# Strain_Gauge_Amplifier.net
KiCad netlist of a schematic drawn in EAGLE
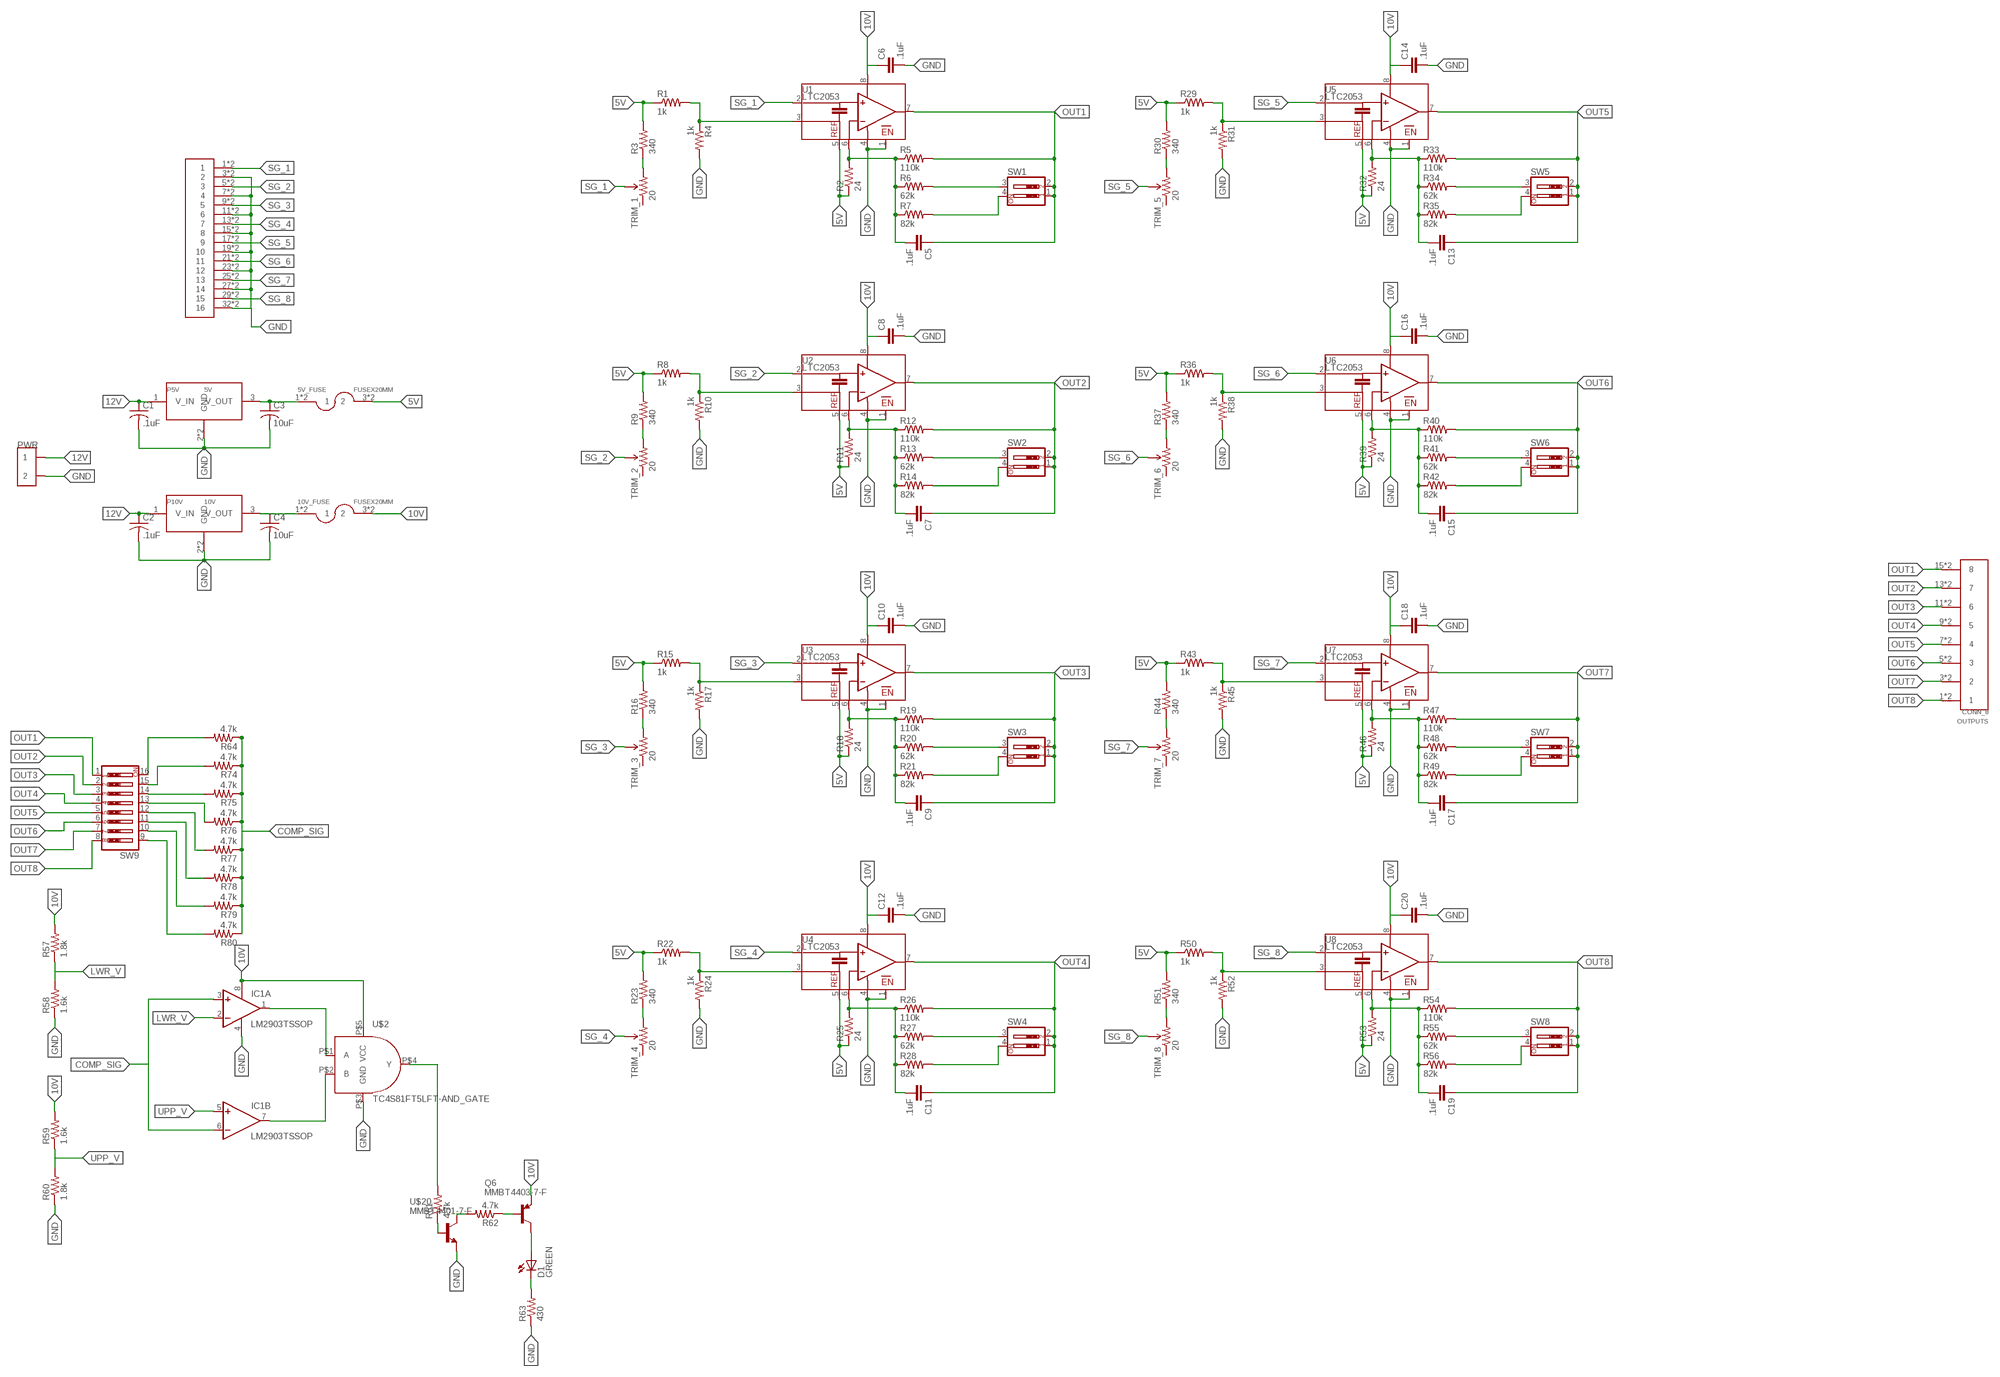
[diagram p0: schematic, sheet 1]

(export (version "E")
  (design (tool "Eeschema 10.0.6"))
  (components
    (comp (ref "5V_FUSE")
      (value "FUSEX20MM")
      (footprint "eagle-import:FUSE_5MM")
      (libsource (lib "eagle-import") (part "FUSEX20MM"))
    )
    (comp (ref "10V_FUSE")
      (value "FUSEX20MM")
      (footprint "eagle-import:FUSE_5MM")
      (libsource (lib "eagle-import") (part "FUSEX20MM"))
    )
    (comp (ref "C1")
      (value ".1uF")
      (footprint "eagle-import:C0603")
      (libsource (lib "eagle-import") (part "C-USC0603"))
    )
    (comp (ref "C2")
      (value ".1uF")
      (footprint "eagle-import:C0603")
      (libsource (lib "eagle-import") (part "C-USC0603"))
    )
    (comp (ref "C3")
      (value "10uF")
      (footprint "eagle-import:C1206")
      (libsource (lib "eagle-import") (part "C-USC1206"))
    )
    (comp (ref "C4")
      (value "10uF")
      (footprint "eagle-import:C1206")
      (libsource (lib "eagle-import") (part "C-USC1206"))
    )
    (comp (ref "C5")
      (value ".1uF")
      (footprint "eagle-import:0603-CAP")
      (libsource (lib "eagle-import") (part "CAP0603-CAP"))
    )
    (comp (ref "C6")
      (value ".1uF")
      (footprint "eagle-import:0603-CAP")
      (libsource (lib "eagle-import") (part "CAP0603-CAP"))
    )
    (comp (ref "C7")
      (value ".1uF")
      (footprint "eagle-import:0603-CAP")
      (libsource (lib "eagle-import") (part "CAP0603-CAP"))
    )
    (comp (ref "C8")
      (value ".1uF")
      (footprint "eagle-import:0603-CAP")
      (libsource (lib "eagle-import") (part "CAP0603-CAP"))
    )
    (comp (ref "C9")
      (value ".1uF")
      (footprint "eagle-import:0603-CAP")
      (libsource (lib "eagle-import") (part "CAP0603-CAP"))
    )
    (comp (ref "C10")
      (value ".1uF")
      (footprint "eagle-import:0603-CAP")
      (libsource (lib "eagle-import") (part "CAP0603-CAP"))
    )
    (comp (ref "C11")
      (value ".1uF")
      (footprint "eagle-import:0603-CAP")
      (libsource (lib "eagle-import") (part "CAP0603-CAP"))
    )
    (comp (ref "C12")
      (value ".1uF")
      (footprint "eagle-import:0603-CAP")
      (libsource (lib "eagle-import") (part "CAP0603-CAP"))
    )
    (comp (ref "C13")
      (value ".1uF")
      (footprint "eagle-import:0603-CAP")
      (libsource (lib "eagle-import") (part "CAP0603-CAP"))
    )
    (comp (ref "C14")
      (value ".1uF")
      (footprint "eagle-import:0603-CAP")
      (libsource (lib "eagle-import") (part "CAP0603-CAP"))
    )
    (comp (ref "C15")
      (value ".1uF")
      (footprint "eagle-import:0603-CAP")
      (libsource (lib "eagle-import") (part "CAP0603-CAP"))
    )
    (comp (ref "C16")
      (value ".1uF")
      (footprint "eagle-import:0603-CAP")
      (libsource (lib "eagle-import") (part "CAP0603-CAP"))
    )
    (comp (ref "C17")
      (value ".1uF")
      (footprint "eagle-import:0603-CAP")
      (libsource (lib "eagle-import") (part "CAP0603-CAP"))
    )
    (comp (ref "C18")
      (value ".1uF")
      (footprint "eagle-import:0603-CAP")
      (libsource (lib "eagle-import") (part "CAP0603-CAP"))
    )
    (comp (ref "C19")
      (value ".1uF")
      (footprint "eagle-import:0603-CAP")
      (libsource (lib "eagle-import") (part "CAP0603-CAP"))
    )
    (comp (ref "C20")
      (value ".1uF")
      (footprint "eagle-import:0603-CAP")
      (libsource (lib "eagle-import") (part "CAP0603-CAP"))
    )
    (comp (ref "D1")
      (value "GREEN")
      (footprint "eagle-import:LED-0603")
      (libsource (lib "eagle-import") (part "LED-GREEN0603"))
    )
    (comp (ref "IC1")
      (value "LM2903TSSOP")
      (footprint "eagle-import:TSSOP8")
      (libsource (lib "eagle-import") (part "LM2903TSSOP"))
    )
    (comp (ref "OUTPUTS")
      (value "CONN_8")
      (footprint "eagle-import:CONNECTOR_8")
      (libsource (lib "eagle-import") (part "CONN_8"))
    )
    (comp (ref "P5V")
      (value "5V")
      (footprint "eagle-import:SOT223")
      (libsource (lib "eagle-import") (part "LM2937"))
    )
    (comp (ref "P10V")
      (value "10V")
      (footprint "eagle-import:SOT223")
      (libsource (lib "eagle-import") (part "LM2937"))
    )
    (comp (ref "PWR")
      (value "CONN_2")
      (footprint "eagle-import:CONNECTOR_2")
      (libsource (lib "eagle-import") (part "CONN_2"))
    )
    (comp (ref "Q6")
      (value "MMBT4403-7-F")
      (footprint "eagle-import:SOT-23-3")
      (libsource (lib "eagle-import") (part "MMBT4403-7-F"))
    )
    (comp (ref "R1")
      (value "1k")
      (footprint "eagle-import:0603-RES")
      (libsource (lib "eagle-import") (part "RESISTOR0603"))
    )
    (comp (ref "R2")
      (value "24")
      (footprint "eagle-import:0603-RES")
      (libsource (lib "eagle-import") (part "RESISTOR0603"))
    )
    (comp (ref "R3")
      (value "340")
      (footprint "eagle-import:0603-RES")
      (libsource (lib "eagle-import") (part "RESISTOR0603"))
    )
    (comp (ref "R4")
      (value "1k")
      (footprint "eagle-import:0603-RES")
      (libsource (lib "eagle-import") (part "RESISTOR0603"))
    )
    (comp (ref "R5")
      (value "110k")
      (footprint "eagle-import:0603-RES")
      (libsource (lib "eagle-import") (part "RESISTOR0603"))
    )
    (comp (ref "R6")
      (value "62k")
      (footprint "eagle-import:0603-RES")
      (libsource (lib "eagle-import") (part "RESISTOR0603"))
    )
    (comp (ref "R7")
      (value "82k")
      (footprint "eagle-import:0603-RES")
      (libsource (lib "eagle-import") (part "RESISTOR0603"))
    )
    (comp (ref "R8")
      (value "1k")
      (footprint "eagle-import:0603-RES")
      (libsource (lib "eagle-import") (part "RESISTOR0603"))
    )
    (comp (ref "R9")
      (value "340")
      (footprint "eagle-import:0603-RES")
      (libsource (lib "eagle-import") (part "RESISTOR0603"))
    )
    (comp (ref "R10")
      (value "1k")
      (footprint "eagle-import:0603-RES")
      (libsource (lib "eagle-import") (part "RESISTOR0603"))
    )
    (comp (ref "R11")
      (value "24")
      (footprint "eagle-import:0603-RES")
      (libsource (lib "eagle-import") (part "RESISTOR0603"))
    )
    (comp (ref "R12")
      (value "110k")
      (footprint "eagle-import:0603-RES")
      (libsource (lib "eagle-import") (part "RESISTOR0603"))
    )
    (comp (ref "R13")
      (value "62k")
      (footprint "eagle-import:0603-RES")
      (libsource (lib "eagle-import") (part "RESISTOR0603"))
    )
    (comp (ref "R14")
      (value "82k")
      (footprint "eagle-import:0603-RES")
      (libsource (lib "eagle-import") (part "RESISTOR0603"))
    )
    (comp (ref "R15")
      (value "1k")
      (footprint "eagle-import:0603-RES")
      (libsource (lib "eagle-import") (part "RESISTOR0603"))
    )
    (comp (ref "R16")
      (value "340")
      (footprint "eagle-import:0603-RES")
      (libsource (lib "eagle-import") (part "RESISTOR0603"))
    )
    (comp (ref "R17")
      (value "1k")
      (footprint "eagle-import:0603-RES")
      (libsource (lib "eagle-import") (part "RESISTOR0603"))
    )
    (comp (ref "R18")
      (value "24")
      (footprint "eagle-import:0603-RES")
      (libsource (lib "eagle-import") (part "RESISTOR0603"))
    )
    (comp (ref "R19")
      (value "110k")
      (footprint "eagle-import:0603-RES")
      (libsource (lib "eagle-import") (part "RESISTOR0603"))
    )
    (comp (ref "R20")
      (value "62k")
      (footprint "eagle-import:0603-RES")
      (libsource (lib "eagle-import") (part "RESISTOR0603"))
    )
    (comp (ref "R21")
      (value "82k")
      (footprint "eagle-import:0603-RES")
      (libsource (lib "eagle-import") (part "RESISTOR0603"))
    )
    (comp (ref "R22")
      (value "1k")
      (footprint "eagle-import:0603-RES")
      (libsource (lib "eagle-import") (part "RESISTOR0603"))
    )
    (comp (ref "R23")
      (value "340")
      (footprint "eagle-import:0603-RES")
      (libsource (lib "eagle-import") (part "RESISTOR0603"))
    )
    (comp (ref "R24")
      (value "1k")
      (footprint "eagle-import:0603-RES")
      (libsource (lib "eagle-import") (part "RESISTOR0603"))
    )
    (comp (ref "R25")
      (value "24")
      (footprint "eagle-import:0603-RES")
      (libsource (lib "eagle-import") (part "RESISTOR0603"))
    )
    (comp (ref "R26")
      (value "110k")
      (footprint "eagle-import:0603-RES")
      (libsource (lib "eagle-import") (part "RESISTOR0603"))
    )
    (comp (ref "R27")
      (value "62k")
      (footprint "eagle-import:0603-RES")
      (libsource (lib "eagle-import") (part "RESISTOR0603"))
    )
    (comp (ref "R28")
      (value "82k")
      (footprint "eagle-import:0603-RES")
      (libsource (lib "eagle-import") (part "RESISTOR0603"))
    )
    (comp (ref "R29")
      (value "1k")
      (footprint "eagle-import:0603-RES")
      (libsource (lib "eagle-import") (part "RESISTOR0603"))
    )
    (comp (ref "R30")
      (value "340")
      (footprint "eagle-import:0603-RES")
      (libsource (lib "eagle-import") (part "RESISTOR0603"))
    )
    (comp (ref "R31")
      (value "1k")
      (footprint "eagle-import:0603-RES")
      (libsource (lib "eagle-import") (part "RESISTOR0603"))
    )
    (comp (ref "R32")
      (value "24")
      (footprint "eagle-import:0603-RES")
      (libsource (lib "eagle-import") (part "RESISTOR0603"))
    )
    (comp (ref "R33")
      (value "110k")
      (footprint "eagle-import:0603-RES")
      (libsource (lib "eagle-import") (part "RESISTOR0603"))
    )
    (comp (ref "R34")
      (value "62k")
      (footprint "eagle-import:0603-RES")
      (libsource (lib "eagle-import") (part "RESISTOR0603"))
    )
    (comp (ref "R35")
      (value "82k")
      (footprint "eagle-import:0603-RES")
      (libsource (lib "eagle-import") (part "RESISTOR0603"))
    )
    (comp (ref "R36")
      (value "1k")
      (footprint "eagle-import:0603-RES")
      (libsource (lib "eagle-import") (part "RESISTOR0603"))
    )
    (comp (ref "R37")
      (value "340")
      (footprint "eagle-import:0603-RES")
      (libsource (lib "eagle-import") (part "RESISTOR0603"))
    )
    (comp (ref "R38")
      (value "1k")
      (footprint "eagle-import:0603-RES")
      (libsource (lib "eagle-import") (part "RESISTOR0603"))
    )
    (comp (ref "R39")
      (value "24")
      (footprint "eagle-import:0603-RES")
      (libsource (lib "eagle-import") (part "RESISTOR0603"))
    )
    (comp (ref "R40")
      (value "110k")
      (footprint "eagle-import:0603-RES")
      (libsource (lib "eagle-import") (part "RESISTOR0603"))
    )
    (comp (ref "R41")
      (value "62k")
      (footprint "eagle-import:0603-RES")
      (libsource (lib "eagle-import") (part "RESISTOR0603"))
    )
    (comp (ref "R42")
      (value "82k")
      (footprint "eagle-import:0603-RES")
      (libsource (lib "eagle-import") (part "RESISTOR0603"))
    )
    (comp (ref "R43")
      (value "1k")
      (footprint "eagle-import:0603-RES")
      (libsource (lib "eagle-import") (part "RESISTOR0603"))
    )
    (comp (ref "R44")
      (value "340")
      (footprint "eagle-import:0603-RES")
      (libsource (lib "eagle-import") (part "RESISTOR0603"))
    )
    (comp (ref "R45")
      (value "1k")
      (footprint "eagle-import:0603-RES")
      (libsource (lib "eagle-import") (part "RESISTOR0603"))
    )
    (comp (ref "R46")
      (value "24")
      (footprint "eagle-import:0603-RES")
      (libsource (lib "eagle-import") (part "RESISTOR0603"))
    )
    (comp (ref "R47")
      (value "110k")
      (footprint "eagle-import:0603-RES")
      (libsource (lib "eagle-import") (part "RESISTOR0603"))
    )
    (comp (ref "R48")
      (value "62k")
      (footprint "eagle-import:0603-RES")
      (libsource (lib "eagle-import") (part "RESISTOR0603"))
    )
    (comp (ref "R49")
      (value "82k")
      (footprint "eagle-import:0603-RES")
      (libsource (lib "eagle-import") (part "RESISTOR0603"))
    )
    (comp (ref "R50")
      (value "1k")
      (footprint "eagle-import:0603-RES")
      (libsource (lib "eagle-import") (part "RESISTOR0603"))
    )
    (comp (ref "R51")
      (value "340")
      (footprint "eagle-import:0603-RES")
      (libsource (lib "eagle-import") (part "RESISTOR0603"))
    )
    (comp (ref "R52")
      (value "1k")
      (footprint "eagle-import:0603-RES")
      (libsource (lib "eagle-import") (part "RESISTOR0603"))
    )
    (comp (ref "R53")
      (value "24")
      (footprint "eagle-import:0603-RES")
      (libsource (lib "eagle-import") (part "RESISTOR0603"))
    )
    (comp (ref "R54")
      (value "110k")
      (footprint "eagle-import:0603-RES")
      (libsource (lib "eagle-import") (part "RESISTOR0603"))
    )
    (comp (ref "R55")
      (value "62k")
      (footprint "eagle-import:0603-RES")
      (libsource (lib "eagle-import") (part "RESISTOR0603"))
    )
    (comp (ref "R56")
      (value "82k")
      (footprint "eagle-import:0603-RES")
      (libsource (lib "eagle-import") (part "RESISTOR0603"))
    )
    (comp (ref "R57")
      (value "1.8k")
      (footprint "eagle-import:0603-RES")
      (libsource (lib "eagle-import") (part "RESISTOR0603"))
    )
    (comp (ref "R58")
      (value "1.6k")
      (footprint "eagle-import:0603-RES")
      (libsource (lib "eagle-import") (part "RESISTOR0603"))
    )
    (comp (ref "R59")
      (value "1.6k")
      (footprint "eagle-import:0603-RES")
      (libsource (lib "eagle-import") (part "RESISTOR0603"))
    )
    (comp (ref "R60")
      (value "1.8k")
      (footprint "eagle-import:0603-RES")
      (libsource (lib "eagle-import") (part "RESISTOR0603"))
    )
    (comp (ref "R61")
      (value "4.7k")
      (footprint "eagle-import:0603-RES")
      (libsource (lib "eagle-import") (part "RESISTOR0603"))
    )
    (comp (ref "R62")
      (value "4.7k")
      (footprint "eagle-import:0603-RES")
      (libsource (lib "eagle-import") (part "RESISTOR0603"))
    )
    (comp (ref "R63")
      (value "430")
      (footprint "eagle-import:0603-RES")
      (libsource (lib "eagle-import") (part "RESISTOR0603"))
    )
    (comp (ref "R64")
      (value "4.7k")
      (footprint "eagle-import:0603-RES")
      (libsource (lib "eagle-import") (part "RESISTOR0603"))
    )
    (comp (ref "R74")
      (value "4.7k")
      (footprint "eagle-import:0603-RES")
      (libsource (lib "eagle-import") (part "RESISTOR0603"))
    )
    (comp (ref "R75")
      (value "4.7k")
      (footprint "eagle-import:0603-RES")
      (libsource (lib "eagle-import") (part "RESISTOR0603"))
    )
    (comp (ref "R76")
      (value "4.7k")
      (footprint "eagle-import:0603-RES")
      (libsource (lib "eagle-import") (part "RESISTOR0603"))
    )
    (comp (ref "R77")
      (value "4.7k")
      (footprint "eagle-import:0603-RES")
      (libsource (lib "eagle-import") (part "RESISTOR0603"))
    )
    (comp (ref "R78")
      (value "4.7k")
      (footprint "eagle-import:0603-RES")
      (libsource (lib "eagle-import") (part "RESISTOR0603"))
    )
    (comp (ref "R79")
      (value "4.7k")
      (footprint "eagle-import:0603-RES")
      (libsource (lib "eagle-import") (part "RESISTOR0603"))
    )
    (comp (ref "R80")
      (value "4.7k")
      (footprint "eagle-import:0603-RES")
      (libsource (lib "eagle-import") (part "RESISTOR0603"))
    )
    (comp (ref "SG_CONN")
      (value "CONN_16")
      (footprint "eagle-import:CONNECTOR_16")
      (libsource (lib "eagle-import") (part "CONN_16"))
    )
    (comp (ref "SW1")
      (value "SW_DIP-2")
      (footprint "eagle-import:DIPSWITCH-02")
      (libsource (lib "eagle-import") (part "SW_DIP-2"))
    )
    (comp (ref "SW2")
      (value "SW_DIP-2")
      (footprint "eagle-import:DIPSWITCH-02")
      (libsource (lib "eagle-import") (part "SW_DIP-2"))
    )
    (comp (ref "SW3")
      (value "SW_DIP-2")
      (footprint "eagle-import:DIPSWITCH-02")
      (libsource (lib "eagle-import") (part "SW_DIP-2"))
    )
    (comp (ref "SW4")
      (value "SW_DIP-2")
      (footprint "eagle-import:DIPSWITCH-02")
      (libsource (lib "eagle-import") (part "SW_DIP-2"))
    )
    (comp (ref "SW5")
      (value "SW_DIP-2")
      (footprint "eagle-import:DIPSWITCH-02")
      (libsource (lib "eagle-import") (part "SW_DIP-2"))
    )
    (comp (ref "SW6")
      (value "SW_DIP-2")
      (footprint "eagle-import:DIPSWITCH-02")
      (libsource (lib "eagle-import") (part "SW_DIP-2"))
    )
    (comp (ref "SW7")
      (value "SW_DIP-2")
      (footprint "eagle-import:DIPSWITCH-02")
      (libsource (lib "eagle-import") (part "SW_DIP-2"))
    )
    (comp (ref "SW8")
      (value "SW_DIP-2")
      (footprint "eagle-import:DIPSWITCH-02")
      (libsource (lib "eagle-import") (part "SW_DIP-2"))
    )
    (comp (ref "SW9")
      (value "SW_DIP-8")
      (footprint "eagle-import:DIPSWITCH-08")
      (libsource (lib "eagle-import") (part "SW_DIP-8"))
    )
    (comp (ref "TRIM_1")
      (value "20")
      (footprint "eagle-import:3926_Y,Z")
      (libsource (lib "eagle-import") (part "3296Y"))
    )
    (comp (ref "TRIM_2")
      (value "20")
      (footprint "eagle-import:3926_Y,Z")
      (libsource (lib "eagle-import") (part "3296Y"))
    )
    (comp (ref "TRIM_3")
      (value "20")
      (footprint "eagle-import:3926_Y,Z")
      (libsource (lib "eagle-import") (part "3296Y"))
    )
    (comp (ref "TRIM_4")
      (value "20")
      (footprint "eagle-import:3926_Y,Z")
      (libsource (lib "eagle-import") (part "3296Y"))
    )
    (comp (ref "TRIM_5")
      (value "20")
      (footprint "eagle-import:3926_Y,Z")
      (libsource (lib "eagle-import") (part "3296Y"))
    )
    (comp (ref "TRIM_6")
      (value "20")
      (footprint "eagle-import:3926_Y,Z")
      (libsource (lib "eagle-import") (part "3296Y"))
    )
    (comp (ref "TRIM_7")
      (value "20")
      (footprint "eagle-import:3926_Y,Z")
      (libsource (lib "eagle-import") (part "3296Y"))
    )
    (comp (ref "TRIM_8")
      (value "20")
      (footprint "eagle-import:3926_Y,Z")
      (libsource (lib "eagle-import") (part "3296Y"))
    )
    (comp (ref "U$2")
      (value "TC4S81FT5LFT-AND_GATE")
      (footprint "eagle-import:SSOP5-P-0.95")
      (libsource (lib "eagle-import") (part "TC4S81FT5LFT-AND_GATE"))
    )
    (comp (ref "U$20")
      (value "MMBT4401-7-F")
      (footprint "eagle-import:SOT-23-3")
      (libsource (lib "eagle-import") (part "MMBT4401-7-F"))
    )
    (comp (ref "U1")
      (value "LTC2053")
      (footprint "eagle-import:MSOP8")
      (libsource (lib "eagle-import") (part "LTC2053"))
    )
    (comp (ref "U2")
      (value "LTC2053")
      (footprint "eagle-import:MSOP8")
      (libsource (lib "eagle-import") (part "LTC2053"))
    )
    (comp (ref "U3")
      (value "LTC2053")
      (footprint "eagle-import:MSOP8")
      (libsource (lib "eagle-import") (part "LTC2053"))
    )
    (comp (ref "U4")
      (value "LTC2053")
      (footprint "eagle-import:MSOP8")
      (libsource (lib "eagle-import") (part "LTC2053"))
    )
    (comp (ref "U5")
      (value "LTC2053")
      (footprint "eagle-import:MSOP8")
      (libsource (lib "eagle-import") (part "LTC2053"))
    )
    (comp (ref "U6")
      (value "LTC2053")
      (footprint "eagle-import:MSOP8")
      (libsource (lib "eagle-import") (part "LTC2053"))
    )
    (comp (ref "U7")
      (value "LTC2053")
      (footprint "eagle-import:MSOP8")
      (libsource (lib "eagle-import") (part "LTC2053"))
    )
    (comp (ref "U8")
      (value "LTC2053")
      (footprint "eagle-import:MSOP8")
      (libsource (lib "eagle-import") (part "LTC2053"))
    )
  )
  (nets
    (net (code "1") (name "5V") (class "Default")
      (node (ref "5V_FUSE") (pin "3") (pinfunction "2_3") (pintype "bidirectional"))
      (node (ref "5V_FUSE") (pin "4") (pinfunction "2_4") (pintype "bidirectional"))
      (node (ref "R1") (pin "1") (pinfunction "1_1") (pintype "passive"))
      (node (ref "R11") (pin "1") (pinfunction "1_1") (pintype "passive"))
      (node (ref "R15") (pin "1") (pinfunction "1_1") (pintype "passive"))
      (node (ref "R16") (pin "2") (pinfunction "2_2") (pintype "passive"))
      (node (ref "R18") (pin "1") (pinfunction "1_1") (pintype "passive"))
      (node (ref "R2") (pin "1") (pinfunction "1_1") (pintype "passive"))
      (node (ref "R22") (pin "1") (pinfunction "1_1") (pintype "passive"))
      (node (ref "R23") (pin "2") (pinfunction "2_2") (pintype "passive"))
      (node (ref "R25") (pin "1") (pinfunction "1_1") (pintype "passive"))
      (node (ref "R29") (pin "1") (pinfunction "1_1") (pintype "passive"))
      (node (ref "R3") (pin "2") (pinfunction "2_2") (pintype "passive"))
      (node (ref "R30") (pin "2") (pinfunction "2_2") (pintype "passive"))
      (node (ref "R32") (pin "1") (pinfunction "1_1") (pintype "passive"))
      (node (ref "R36") (pin "1") (pinfunction "1_1") (pintype "passive"))
      (node (ref "R37") (pin "2") (pinfunction "2_2") (pintype "passive"))
      (node (ref "R39") (pin "1") (pinfunction "1_1") (pintype "passive"))
      (node (ref "R43") (pin "1") (pinfunction "1_1") (pintype "passive"))
      (node (ref "R44") (pin "2") (pinfunction "2_2") (pintype "passive"))
      (node (ref "R46") (pin "1") (pinfunction "1_1") (pintype "passive"))
      (node (ref "R50") (pin "1") (pinfunction "1_1") (pintype "passive"))
      (node (ref "R51") (pin "2") (pinfunction "2_2") (pintype "passive"))
      (node (ref "R53") (pin "1") (pinfunction "1_1") (pintype "passive"))
      (node (ref "R8") (pin "1") (pinfunction "1_1") (pintype "passive"))
      (node (ref "R9") (pin "2") (pinfunction "2_2") (pintype "passive"))
      (node (ref "U1") (pin "5") (pinfunction "REF_5") (pintype "bidirectional"))
      (node (ref "U2") (pin "5") (pinfunction "REF_5") (pintype "bidirectional"))
      (node (ref "U3") (pin "5") (pinfunction "REF_5") (pintype "bidirectional"))
      (node (ref "U4") (pin "5") (pinfunction "REF_5") (pintype "bidirectional"))
      (node (ref "U5") (pin "5") (pinfunction "REF_5") (pintype "bidirectional"))
      (node (ref "U6") (pin "5") (pinfunction "REF_5") (pintype "bidirectional"))
      (node (ref "U7") (pin "5") (pinfunction "REF_5") (pintype "bidirectional"))
      (node (ref "U8") (pin "5") (pinfunction "REF_5") (pintype "bidirectional"))
    )
    (net (code "2") (name "10V") (class "Default")
      (node (ref "10V_FUSE") (pin "3") (pinfunction "2_3") (pintype "bidirectional"))
      (node (ref "10V_FUSE") (pin "4") (pinfunction "2_4") (pintype "bidirectional"))
      (node (ref "C10") (pin "1") (pinfunction "1_1") (pintype "passive"))
      (node (ref "C12") (pin "1") (pinfunction "1_1") (pintype "passive"))
      (node (ref "C14") (pin "1") (pinfunction "1_1") (pintype "passive"))
      (node (ref "C16") (pin "1") (pinfunction "1_1") (pintype "passive"))
      (node (ref "C18") (pin "1") (pinfunction "1_1") (pintype "passive"))
      (node (ref "C20") (pin "1") (pinfunction "1_1") (pintype "passive"))
      (node (ref "C6") (pin "1") (pinfunction "1_1") (pintype "passive"))
      (node (ref "C8") (pin "1") (pinfunction "1_1") (pintype "passive"))
      (node (ref "IC1") (pin "8") (pinfunction "V+_8") (pintype "power_in"))
      (node (ref "Q6") (pin "P$3") (pinfunction "E_P$3") (pintype "passive"))
      (node (ref "R57") (pin "2") (pinfunction "2_2") (pintype "passive"))
      (node (ref "R59") (pin "2") (pinfunction "2_2") (pintype "passive"))
      (node (ref "U$2") (pin "P$5") (pinfunction "VCC_P$5") (pintype "bidirectional"))
      (node (ref "U1") (pin "8") (pinfunction "V+_8") (pintype "power_in"))
      (node (ref "U2") (pin "8") (pinfunction "V+_8") (pintype "power_in"))
      (node (ref "U3") (pin "8") (pinfunction "V+_8") (pintype "power_in"))
      (node (ref "U4") (pin "8") (pinfunction "V+_8") (pintype "power_in"))
      (node (ref "U5") (pin "8") (pinfunction "V+_8") (pintype "power_in"))
      (node (ref "U6") (pin "8") (pinfunction "V+_8") (pintype "power_in"))
      (node (ref "U7") (pin "8") (pinfunction "V+_8") (pintype "power_in"))
      (node (ref "U8") (pin "8") (pinfunction "V+_8") (pintype "power_in"))
    )
    (net (code "3") (name "12V") (class "Default")
      (node (ref "C1") (pin "1") (pinfunction "1_1") (pintype "passive"))
      (node (ref "C2") (pin "1") (pinfunction "1_1") (pintype "passive"))
      (node (ref "P10V") (pin "1") (pinfunction "V_IN_1") (pintype "power_in"))
      (node (ref "P5V") (pin "1") (pinfunction "V_IN_1") (pintype "power_in"))
      (node (ref "PWR") (pin "1") (pinfunction "1_1") (pintype "bidirectional"))
      (node (ref "PWR") (pin "2") (pinfunction "1_2") (pintype "bidirectional"))
    )
    (net (code "4") (name "COMP_SIG") (class "Default")
      (node (ref "IC1") (pin "3") (pinfunction "+IN_3") (pintype "input"))
      (node (ref "IC1") (pin "6") (pinfunction "-IN_6") (pintype "input"))
      (node (ref "R64") (pin "1") (pinfunction "1_1") (pintype "passive"))
      (node (ref "R74") (pin "1") (pinfunction "1_1") (pintype "passive"))
      (node (ref "R75") (pin "1") (pinfunction "1_1") (pintype "passive"))
      (node (ref "R76") (pin "1") (pinfunction "1_1") (pintype "passive"))
      (node (ref "R77") (pin "1") (pinfunction "1_1") (pintype "passive"))
      (node (ref "R78") (pin "1") (pinfunction "1_1") (pintype "passive"))
      (node (ref "R79") (pin "1") (pinfunction "1_1") (pintype "passive"))
      (node (ref "R80") (pin "1") (pinfunction "1_1") (pintype "passive"))
    )
    (net (code "5") (name "GND") (class "Default")
      (node (ref "C1") (pin "2") (pinfunction "2_2") (pintype "passive"))
      (node (ref "C10") (pin "2") (pinfunction "2_2") (pintype "passive"))
      (node (ref "C12") (pin "2") (pinfunction "2_2") (pintype "passive"))
      (node (ref "C14") (pin "2") (pinfunction "2_2") (pintype "passive"))
      (node (ref "C16") (pin "2") (pinfunction "2_2") (pintype "passive"))
      (node (ref "C18") (pin "2") (pinfunction "2_2") (pintype "passive"))
      (node (ref "C2") (pin "2") (pinfunction "2_2") (pintype "passive"))
      (node (ref "C20") (pin "2") (pinfunction "2_2") (pintype "passive"))
      (node (ref "C3") (pin "2") (pinfunction "2_2") (pintype "passive"))
      (node (ref "C4") (pin "2") (pinfunction "2_2") (pintype "passive"))
      (node (ref "C6") (pin "2") (pinfunction "2_2") (pintype "passive"))
      (node (ref "C8") (pin "2") (pinfunction "2_2") (pintype "passive"))
      (node (ref "IC1") (pin "4") (pinfunction "V-_4") (pintype "power_in"))
      (node (ref "P10V") (pin "2") (pinfunction "GND_2") (pintype "power_in"))
      (node (ref "P10V") (pin "4") (pinfunction "GND_4") (pintype "power_in"))
      (node (ref "P5V") (pin "2") (pinfunction "GND_2") (pintype "power_in"))
      (node (ref "P5V") (pin "4") (pinfunction "GND_4") (pintype "power_in"))
      (node (ref "PWR") (pin "3") (pinfunction "2_3") (pintype "bidirectional"))
      (node (ref "PWR") (pin "4") (pinfunction "2_4") (pintype "bidirectional"))
      (node (ref "R10") (pin "2") (pinfunction "2_2") (pintype "passive"))
      (node (ref "R17") (pin "2") (pinfunction "2_2") (pintype "passive"))
      (node (ref "R24") (pin "2") (pinfunction "2_2") (pintype "passive"))
      (node (ref "R31") (pin "2") (pinfunction "2_2") (pintype "passive"))
      (node (ref "R38") (pin "2") (pinfunction "2_2") (pintype "passive"))
      (node (ref "R4") (pin "2") (pinfunction "2_2") (pintype "passive"))
      (node (ref "R45") (pin "2") (pinfunction "2_2") (pintype "passive"))
      (node (ref "R52") (pin "2") (pinfunction "2_2") (pintype "passive"))
      (node (ref "R58") (pin "1") (pinfunction "1_1") (pintype "passive"))
      (node (ref "R60") (pin "1") (pinfunction "1_1") (pintype "passive"))
      (node (ref "R63") (pin "1") (pinfunction "1_1") (pintype "passive"))
      (node (ref "SG_CONN") (pin "11") (pinfunction "6_11") (pintype "bidirectional"))
      (node (ref "SG_CONN") (pin "12") (pinfunction "6_12") (pintype "bidirectional"))
      (node (ref "SG_CONN") (pin "15") (pinfunction "8_15") (pintype "bidirectional"))
      (node (ref "SG_CONN") (pin "16") (pinfunction "8_16") (pintype "bidirectional"))
      (node (ref "SG_CONN") (pin "19") (pinfunction "10_19") (pintype "bidirectional"))
      (node (ref "SG_CONN") (pin "20") (pinfunction "10_20") (pintype "bidirectional"))
      (node (ref "SG_CONN") (pin "23") (pinfunction "12_23") (pintype "bidirectional"))
      (node (ref "SG_CONN") (pin "24") (pinfunction "12_24") (pintype "bidirectional"))
      (node (ref "SG_CONN") (pin "27") (pinfunction "14_27") (pintype "bidirectional"))
      (node (ref "SG_CONN") (pin "28") (pinfunction "14_28") (pintype "bidirectional"))
      (node (ref "SG_CONN") (pin "3") (pinfunction "2_3") (pintype "bidirectional"))
      (node (ref "SG_CONN") (pin "32") (pinfunction "16_32") (pintype "bidirectional"))
      (node (ref "SG_CONN") (pin "4") (pinfunction "2_4") (pintype "bidirectional"))
      (node (ref "SG_CONN") (pin "7") (pinfunction "4_7") (pintype "bidirectional"))
      (node (ref "SG_CONN") (pin "8") (pinfunction "4_8") (pintype "bidirectional"))
      (node (ref "SG_CONN") (pin "P31") (pinfunction "16_P31") (pintype "bidirectional"))
      (node (ref "U$2") (pin "P$3") (pinfunction "GND_P$3") (pintype "bidirectional"))
      (node (ref "U$20") (pin "P$3") (pinfunction "E_P$3") (pintype "passive"))
      (node (ref "U1") (pin "1") (pinfunction "EN_1") (pintype "input"))
      (node (ref "U1") (pin "4") (pinfunction "V-_4") (pintype "power_in"))
      (node (ref "U2") (pin "1") (pinfunction "EN_1") (pintype "input"))
      (node (ref "U2") (pin "4") (pinfunction "V-_4") (pintype "power_in"))
      (node (ref "U3") (pin "1") (pinfunction "EN_1") (pintype "input"))
      (node (ref "U3") (pin "4") (pinfunction "V-_4") (pintype "power_in"))
      (node (ref "U4") (pin "1") (pinfunction "EN_1") (pintype "input"))
      (node (ref "U4") (pin "4") (pinfunction "V-_4") (pintype "power_in"))
      (node (ref "U5") (pin "1") (pinfunction "EN_1") (pintype "input"))
      (node (ref "U5") (pin "4") (pinfunction "V-_4") (pintype "power_in"))
      (node (ref "U6") (pin "1") (pinfunction "EN_1") (pintype "input"))
      (node (ref "U6") (pin "4") (pinfunction "V-_4") (pintype "power_in"))
      (node (ref "U7") (pin "1") (pinfunction "EN_1") (pintype "input"))
      (node (ref "U7") (pin "4") (pinfunction "V-_4") (pintype "power_in"))
      (node (ref "U8") (pin "1") (pinfunction "EN_1") (pintype "input"))
      (node (ref "U8") (pin "4") (pinfunction "V-_4") (pintype "power_in"))
    )
    (net (code "6") (name "LWR_V") (class "Default")
      (node (ref "IC1") (pin "2") (pinfunction "-IN_2") (pintype "input"))
      (node (ref "R57") (pin "1") (pinfunction "1_1") (pintype "passive"))
      (node (ref "R58") (pin "2") (pinfunction "2_2") (pintype "passive"))
    )
    (net (code "7") (name "Net-(D1-PadC)") (class "Default")
      (node (ref "D1") (pin "C") (pinfunction "C_C") (pintype "passive"))
      (node (ref "R63") (pin "2") (pinfunction "2_2") (pintype "passive"))
    )
    (net (code "8") (name "Net-(IC1A-OUT)") (class "Default")
      (node (ref "IC1") (pin "1") (pinfunction "OUT_1") (pintype "output"))
      (node (ref "U$2") (pin "P$1") (pinfunction "A_P$1") (pintype "bidirectional"))
    )
    (net (code "9") (name "Net-(IC1B-OUT)") (class "Default")
      (node (ref "IC1") (pin "7") (pinfunction "OUT_7") (pintype "output"))
      (node (ref "U$2") (pin "P$2") (pinfunction "B_P$2") (pintype "bidirectional"))
    )
    (net (code "10") (name "Net-(P5V-V_OUT)") (class "Default")
      (node (ref "5V_FUSE") (pin "1") (pinfunction "1_1") (pintype "bidirectional"))
      (node (ref "5V_FUSE") (pin "2") (pinfunction "1_2") (pintype "bidirectional"))
      (node (ref "C3") (pin "1") (pinfunction "1_1") (pintype "passive"))
      (node (ref "P5V") (pin "3") (pinfunction "V_OUT_3") (pintype "output"))
    )
    (net (code "11") (name "Net-(P10V-V_OUT)") (class "Default")
      (node (ref "10V_FUSE") (pin "1") (pinfunction "1_1") (pintype "bidirectional"))
      (node (ref "10V_FUSE") (pin "2") (pinfunction "1_2") (pintype "bidirectional"))
      (node (ref "C4") (pin "1") (pinfunction "1_1") (pintype "passive"))
      (node (ref "P10V") (pin "3") (pinfunction "V_OUT_3") (pintype "output"))
    )
    (net (code "12") (name "Net-(Q6-B)") (class "Default")
      (node (ref "Q6") (pin "P$2") (pinfunction "B_P$2") (pintype "passive"))
      (node (ref "R62") (pin "1") (pinfunction "1_1") (pintype "passive"))
    )
    (net (code "13") (name "Net-(Q6-C)") (class "Default")
      (node (ref "D1") (pin "A") (pinfunction "A_A") (pintype "passive"))
      (node (ref "Q6") (pin "P$1") (pinfunction "C_P$1") (pintype "passive"))
    )
    (net (code "14") (name "Net-(R6-Pad2)") (class "Default")
      (node (ref "R6") (pin "2") (pinfunction "2_2") (pintype "passive"))
      (node (ref "SW1") (pin "3") (pinfunction "3_3") (pintype "passive"))
    )
    (net (code "15") (name "Net-(R7-Pad2)") (class "Default")
      (node (ref "R7") (pin "2") (pinfunction "2_2") (pintype "passive"))
      (node (ref "SW1") (pin "4") (pinfunction "4_4") (pintype "passive"))
    )
    (net (code "16") (name "Net-(R13-Pad2)") (class "Default")
      (node (ref "R13") (pin "2") (pinfunction "2_2") (pintype "passive"))
      (node (ref "SW2") (pin "3") (pinfunction "3_3") (pintype "passive"))
    )
    (net (code "17") (name "Net-(R14-Pad2)") (class "Default")
      (node (ref "R14") (pin "2") (pinfunction "2_2") (pintype "passive"))
      (node (ref "SW2") (pin "4") (pinfunction "4_4") (pintype "passive"))
    )
    (net (code "18") (name "Net-(R20-Pad2)") (class "Default")
      (node (ref "R20") (pin "2") (pinfunction "2_2") (pintype "passive"))
      (node (ref "SW3") (pin "3") (pinfunction "3_3") (pintype "passive"))
    )
    (net (code "19") (name "Net-(R21-Pad2)") (class "Default")
      (node (ref "R21") (pin "2") (pinfunction "2_2") (pintype "passive"))
      (node (ref "SW3") (pin "4") (pinfunction "4_4") (pintype "passive"))
    )
    (net (code "20") (name "Net-(R27-Pad2)") (class "Default")
      (node (ref "R27") (pin "2") (pinfunction "2_2") (pintype "passive"))
      (node (ref "SW4") (pin "3") (pinfunction "3_3") (pintype "passive"))
    )
    (net (code "21") (name "Net-(R28-Pad2)") (class "Default")
      (node (ref "R28") (pin "2") (pinfunction "2_2") (pintype "passive"))
      (node (ref "SW4") (pin "4") (pinfunction "4_4") (pintype "passive"))
    )
    (net (code "22") (name "Net-(R34-Pad2)") (class "Default")
      (node (ref "R34") (pin "2") (pinfunction "2_2") (pintype "passive"))
      (node (ref "SW5") (pin "3") (pinfunction "3_3") (pintype "passive"))
    )
    (net (code "23") (name "Net-(R35-Pad2)") (class "Default")
      (node (ref "R35") (pin "2") (pinfunction "2_2") (pintype "passive"))
      (node (ref "SW5") (pin "4") (pinfunction "4_4") (pintype "passive"))
    )
    (net (code "24") (name "Net-(R41-Pad2)") (class "Default")
      (node (ref "R41") (pin "2") (pinfunction "2_2") (pintype "passive"))
      (node (ref "SW6") (pin "3") (pinfunction "3_3") (pintype "passive"))
    )
    (net (code "25") (name "Net-(R42-Pad2)") (class "Default")
      (node (ref "R42") (pin "2") (pinfunction "2_2") (pintype "passive"))
      (node (ref "SW6") (pin "4") (pinfunction "4_4") (pintype "passive"))
    )
    (net (code "26") (name "Net-(R48-Pad2)") (class "Default")
      (node (ref "R48") (pin "2") (pinfunction "2_2") (pintype "passive"))
      (node (ref "SW7") (pin "3") (pinfunction "3_3") (pintype "passive"))
    )
    (net (code "27") (name "Net-(R49-Pad2)") (class "Default")
      (node (ref "R49") (pin "2") (pinfunction "2_2") (pintype "passive"))
      (node (ref "SW7") (pin "4") (pinfunction "4_4") (pintype "passive"))
    )
    (net (code "28") (name "Net-(R55-Pad2)") (class "Default")
      (node (ref "R55") (pin "2") (pinfunction "2_2") (pintype "passive"))
      (node (ref "SW8") (pin "3") (pinfunction "3_3") (pintype "passive"))
    )
    (net (code "29") (name "Net-(R56-Pad2)") (class "Default")
      (node (ref "R56") (pin "2") (pinfunction "2_2") (pintype "passive"))
      (node (ref "SW8") (pin "4") (pinfunction "4_4") (pintype "passive"))
    )
    (net (code "30") (name "Net-(R64-Pad2)") (class "Default")
      (node (ref "R64") (pin "2") (pinfunction "2_2") (pintype "passive"))
      (node (ref "SW9") (pin "16") (pinfunction "16_16") (pintype "passive"))
    )
    (net (code "31") (name "Net-(R74-Pad2)") (class "Default")
      (node (ref "R74") (pin "2") (pinfunction "2_2") (pintype "passive"))
      (node (ref "SW9") (pin "15") (pinfunction "15_15") (pintype "passive"))
    )
    (net (code "32") (name "Net-(R75-Pad2)") (class "Default")
      (node (ref "R75") (pin "2") (pinfunction "2_2") (pintype "passive"))
      (node (ref "SW9") (pin "14") (pinfunction "14_14") (pintype "passive"))
    )
    (net (code "33") (name "Net-(R76-Pad2)") (class "Default")
      (node (ref "R76") (pin "2") (pinfunction "2_2") (pintype "passive"))
      (node (ref "SW9") (pin "13") (pinfunction "13_13") (pintype "passive"))
    )
    (net (code "34") (name "Net-(R77-Pad2)") (class "Default")
      (node (ref "R77") (pin "2") (pinfunction "2_2") (pintype "passive"))
      (node (ref "SW9") (pin "12") (pinfunction "12_12") (pintype "passive"))
    )
    (net (code "35") (name "Net-(R78-Pad2)") (class "Default")
      (node (ref "R78") (pin "2") (pinfunction "2_2") (pintype "passive"))
      (node (ref "SW9") (pin "11") (pinfunction "11_11") (pintype "passive"))
    )
    (net (code "36") (name "Net-(R79-Pad2)") (class "Default")
      (node (ref "R79") (pin "2") (pinfunction "2_2") (pintype "passive"))
      (node (ref "SW9") (pin "10") (pinfunction "10_10") (pintype "passive"))
    )
    (net (code "37") (name "Net-(R80-Pad2)") (class "Default")
      (node (ref "R80") (pin "2") (pinfunction "2_2") (pintype "passive"))
      (node (ref "SW9") (pin "9") (pinfunction "9_9") (pintype "passive"))
    )
    (net (code "38") (name "Net-(TRIM_1-CW)") (class "Default")
      (node (ref "R3") (pin "1") (pinfunction "1_1") (pintype "passive"))
      (node (ref "TRIM_1") (pin "3") (pinfunction "CW_3") (pintype "passive"))
    )
    (net (code "39") (name "Net-(TRIM_2-CW)") (class "Default")
      (node (ref "R9") (pin "1") (pinfunction "1_1") (pintype "passive"))
      (node (ref "TRIM_2") (pin "3") (pinfunction "CW_3") (pintype "passive"))
    )
    (net (code "40") (name "Net-(TRIM_3-CW)") (class "Default")
      (node (ref "R16") (pin "1") (pinfunction "1_1") (pintype "passive"))
      (node (ref "TRIM_3") (pin "3") (pinfunction "CW_3") (pintype "passive"))
    )
    (net (code "41") (name "Net-(TRIM_4-CW)") (class "Default")
      (node (ref "R23") (pin "1") (pinfunction "1_1") (pintype "passive"))
      (node (ref "TRIM_4") (pin "3") (pinfunction "CW_3") (pintype "passive"))
    )
    (net (code "42") (name "Net-(TRIM_5-CW)") (class "Default")
      (node (ref "R30") (pin "1") (pinfunction "1_1") (pintype "passive"))
      (node (ref "TRIM_5") (pin "3") (pinfunction "CW_3") (pintype "passive"))
    )
    (net (code "43") (name "Net-(TRIM_6-CW)") (class "Default")
      (node (ref "R37") (pin "1") (pinfunction "1_1") (pintype "passive"))
      (node (ref "TRIM_6") (pin "3") (pinfunction "CW_3") (pintype "passive"))
    )
    (net (code "44") (name "Net-(TRIM_7-CW)") (class "Default")
      (node (ref "R44") (pin "1") (pinfunction "1_1") (pintype "passive"))
      (node (ref "TRIM_7") (pin "3") (pinfunction "CW_3") (pintype "passive"))
    )
    (net (code "45") (name "Net-(TRIM_8-CW)") (class "Default")
      (node (ref "R51") (pin "1") (pinfunction "1_1") (pintype "passive"))
      (node (ref "TRIM_8") (pin "3") (pinfunction "CW_3") (pintype "passive"))
    )
    (net (code "46") (name "Net-(U$2-Y)") (class "Default")
      (node (ref "R61") (pin "2") (pinfunction "2_2") (pintype "passive"))
      (node (ref "U$2") (pin "P$4") (pinfunction "Y_P$4") (pintype "bidirectional"))
    )
    (net (code "47") (name "Net-(U$20-B)") (class "Default")
      (node (ref "R61") (pin "1") (pinfunction "1_1") (pintype "passive"))
      (node (ref "U$20") (pin "P$2") (pinfunction "B_P$2") (pintype "passive"))
    )
    (net (code "48") (name "Net-(U$20-C)") (class "Default")
      (node (ref "R62") (pin "2") (pinfunction "2_2") (pintype "passive"))
      (node (ref "U$20") (pin "P$1") (pinfunction "C_P$1") (pintype "passive"))
    )
    (net (code "49") (name "Net-(U1-+IN)") (class "Default")
      (node (ref "R1") (pin "2") (pinfunction "2_2") (pintype "passive"))
      (node (ref "R4") (pin "1") (pinfunction "1_1") (pintype "passive"))
      (node (ref "U1") (pin "3") (pinfunction "+IN_3") (pintype "input"))
    )
    (net (code "50") (name "Net-(U1-RG)") (class "Default")
      (node (ref "C5") (pin "2") (pinfunction "2_2") (pintype "passive"))
      (node (ref "R2") (pin "2") (pinfunction "2_2") (pintype "passive"))
      (node (ref "R5") (pin "1") (pinfunction "1_1") (pintype "passive"))
      (node (ref "R6") (pin "1") (pinfunction "1_1") (pintype "passive"))
      (node (ref "R7") (pin "1") (pinfunction "1_1") (pintype "passive"))
      (node (ref "U1") (pin "6") (pinfunction "RG_6") (pintype "bidirectional"))
    )
    (net (code "51") (name "Net-(U2-+IN)") (class "Default")
      (node (ref "R10") (pin "1") (pinfunction "1_1") (pintype "passive"))
      (node (ref "R8") (pin "2") (pinfunction "2_2") (pintype "passive"))
      (node (ref "U2") (pin "3") (pinfunction "+IN_3") (pintype "input"))
    )
    (net (code "52") (name "Net-(U2-RG)") (class "Default")
      (node (ref "C7") (pin "2") (pinfunction "2_2") (pintype "passive"))
      (node (ref "R11") (pin "2") (pinfunction "2_2") (pintype "passive"))
      (node (ref "R12") (pin "1") (pinfunction "1_1") (pintype "passive"))
      (node (ref "R13") (pin "1") (pinfunction "1_1") (pintype "passive"))
      (node (ref "R14") (pin "1") (pinfunction "1_1") (pintype "passive"))
      (node (ref "U2") (pin "6") (pinfunction "RG_6") (pintype "bidirectional"))
    )
    (net (code "53") (name "Net-(U3-+IN)") (class "Default")
      (node (ref "R15") (pin "2") (pinfunction "2_2") (pintype "passive"))
      (node (ref "R17") (pin "1") (pinfunction "1_1") (pintype "passive"))
      (node (ref "U3") (pin "3") (pinfunction "+IN_3") (pintype "input"))
    )
    (net (code "54") (name "Net-(U3-RG)") (class "Default")
      (node (ref "C9") (pin "2") (pinfunction "2_2") (pintype "passive"))
      (node (ref "R18") (pin "2") (pinfunction "2_2") (pintype "passive"))
      (node (ref "R19") (pin "1") (pinfunction "1_1") (pintype "passive"))
      (node (ref "R20") (pin "1") (pinfunction "1_1") (pintype "passive"))
      (node (ref "R21") (pin "1") (pinfunction "1_1") (pintype "passive"))
      (node (ref "U3") (pin "6") (pinfunction "RG_6") (pintype "bidirectional"))
    )
    (net (code "55") (name "Net-(U4-+IN)") (class "Default")
      (node (ref "R22") (pin "2") (pinfunction "2_2") (pintype "passive"))
      (node (ref "R24") (pin "1") (pinfunction "1_1") (pintype "passive"))
      (node (ref "U4") (pin "3") (pinfunction "+IN_3") (pintype "input"))
    )
    (net (code "56") (name "Net-(U4-RG)") (class "Default")
      (node (ref "C11") (pin "2") (pinfunction "2_2") (pintype "passive"))
      (node (ref "R25") (pin "2") (pinfunction "2_2") (pintype "passive"))
      (node (ref "R26") (pin "1") (pinfunction "1_1") (pintype "passive"))
      (node (ref "R27") (pin "1") (pinfunction "1_1") (pintype "passive"))
      (node (ref "R28") (pin "1") (pinfunction "1_1") (pintype "passive"))
      (node (ref "U4") (pin "6") (pinfunction "RG_6") (pintype "bidirectional"))
    )
    (net (code "57") (name "Net-(U5-+IN)") (class "Default")
      (node (ref "R29") (pin "2") (pinfunction "2_2") (pintype "passive"))
      (node (ref "R31") (pin "1") (pinfunction "1_1") (pintype "passive"))
      (node (ref "U5") (pin "3") (pinfunction "+IN_3") (pintype "input"))
    )
    (net (code "58") (name "Net-(U5-RG)") (class "Default")
      (node (ref "C13") (pin "2") (pinfunction "2_2") (pintype "passive"))
      (node (ref "R32") (pin "2") (pinfunction "2_2") (pintype "passive"))
      (node (ref "R33") (pin "1") (pinfunction "1_1") (pintype "passive"))
      (node (ref "R34") (pin "1") (pinfunction "1_1") (pintype "passive"))
      (node (ref "R35") (pin "1") (pinfunction "1_1") (pintype "passive"))
      (node (ref "U5") (pin "6") (pinfunction "RG_6") (pintype "bidirectional"))
    )
    (net (code "59") (name "Net-(U6-+IN)") (class "Default")
      (node (ref "R36") (pin "2") (pinfunction "2_2") (pintype "passive"))
      (node (ref "R38") (pin "1") (pinfunction "1_1") (pintype "passive"))
      (node (ref "U6") (pin "3") (pinfunction "+IN_3") (pintype "input"))
    )
    (net (code "60") (name "Net-(U6-RG)") (class "Default")
      (node (ref "C15") (pin "2") (pinfunction "2_2") (pintype "passive"))
      (node (ref "R39") (pin "2") (pinfunction "2_2") (pintype "passive"))
      (node (ref "R40") (pin "1") (pinfunction "1_1") (pintype "passive"))
      (node (ref "R41") (pin "1") (pinfunction "1_1") (pintype "passive"))
      (node (ref "R42") (pin "1") (pinfunction "1_1") (pintype "passive"))
      (node (ref "U6") (pin "6") (pinfunction "RG_6") (pintype "bidirectional"))
    )
    (net (code "61") (name "Net-(U7-+IN)") (class "Default")
      (node (ref "R43") (pin "2") (pinfunction "2_2") (pintype "passive"))
      (node (ref "R45") (pin "1") (pinfunction "1_1") (pintype "passive"))
      (node (ref "U7") (pin "3") (pinfunction "+IN_3") (pintype "input"))
    )
    (net (code "62") (name "Net-(U7-RG)") (class "Default")
      (node (ref "C17") (pin "2") (pinfunction "2_2") (pintype "passive"))
      (node (ref "R46") (pin "2") (pinfunction "2_2") (pintype "passive"))
      (node (ref "R47") (pin "1") (pinfunction "1_1") (pintype "passive"))
      (node (ref "R48") (pin "1") (pinfunction "1_1") (pintype "passive"))
      (node (ref "R49") (pin "1") (pinfunction "1_1") (pintype "passive"))
      (node (ref "U7") (pin "6") (pinfunction "RG_6") (pintype "bidirectional"))
    )
    (net (code "63") (name "Net-(U8-+IN)") (class "Default")
      (node (ref "R50") (pin "2") (pinfunction "2_2") (pintype "passive"))
      (node (ref "R52") (pin "1") (pinfunction "1_1") (pintype "passive"))
      (node (ref "U8") (pin "3") (pinfunction "+IN_3") (pintype "input"))
    )
    (net (code "64") (name "Net-(U8-RG)") (class "Default")
      (node (ref "C19") (pin "2") (pinfunction "2_2") (pintype "passive"))
      (node (ref "R53") (pin "2") (pinfunction "2_2") (pintype "passive"))
      (node (ref "R54") (pin "1") (pinfunction "1_1") (pintype "passive"))
      (node (ref "R55") (pin "1") (pinfunction "1_1") (pintype "passive"))
      (node (ref "R56") (pin "1") (pinfunction "1_1") (pintype "passive"))
      (node (ref "U8") (pin "6") (pinfunction "RG_6") (pintype "bidirectional"))
    )
    (net (code "65") (name "OUT1") (class "Default")
      (node (ref "C5") (pin "1") (pinfunction "1_1") (pintype "passive"))
      (node (ref "OUTPUTS") (pin "15") (pinfunction "8_15") (pintype "bidirectional"))
      (node (ref "OUTPUTS") (pin "16") (pinfunction "8_16") (pintype "bidirectional"))
      (node (ref "R5") (pin "2") (pinfunction "2_2") (pintype "passive"))
      (node (ref "SW1") (pin "1") (pinfunction "1_1") (pintype "passive"))
      (node (ref "SW1") (pin "2") (pinfunction "2_2") (pintype "passive"))
      (node (ref "SW9") (pin "1") (pinfunction "1_1") (pintype "passive"))
      (node (ref "U1") (pin "7") (pinfunction "OUT_7") (pintype "output"))
    )
    (net (code "66") (name "OUT2") (class "Default")
      (node (ref "C7") (pin "1") (pinfunction "1_1") (pintype "passive"))
      (node (ref "OUTPUTS") (pin "13") (pinfunction "7_13") (pintype "bidirectional"))
      (node (ref "OUTPUTS") (pin "14") (pinfunction "7_14") (pintype "bidirectional"))
      (node (ref "R12") (pin "2") (pinfunction "2_2") (pintype "passive"))
      (node (ref "SW2") (pin "1") (pinfunction "1_1") (pintype "passive"))
      (node (ref "SW2") (pin "2") (pinfunction "2_2") (pintype "passive"))
      (node (ref "SW9") (pin "2") (pinfunction "2_2") (pintype "passive"))
      (node (ref "U2") (pin "7") (pinfunction "OUT_7") (pintype "output"))
    )
    (net (code "67") (name "OUT3") (class "Default")
      (node (ref "C9") (pin "1") (pinfunction "1_1") (pintype "passive"))
      (node (ref "OUTPUTS") (pin "11") (pinfunction "6_11") (pintype "bidirectional"))
      (node (ref "OUTPUTS") (pin "12") (pinfunction "6_12") (pintype "bidirectional"))
      (node (ref "R19") (pin "2") (pinfunction "2_2") (pintype "passive"))
      (node (ref "SW3") (pin "1") (pinfunction "1_1") (pintype "passive"))
      (node (ref "SW3") (pin "2") (pinfunction "2_2") (pintype "passive"))
      (node (ref "SW9") (pin "3") (pinfunction "3_3") (pintype "passive"))
      (node (ref "U3") (pin "7") (pinfunction "OUT_7") (pintype "output"))
    )
    (net (code "68") (name "OUT4") (class "Default")
      (node (ref "C11") (pin "1") (pinfunction "1_1") (pintype "passive"))
      (node (ref "OUTPUTS") (pin "10") (pinfunction "5_10") (pintype "bidirectional"))
      (node (ref "OUTPUTS") (pin "9") (pinfunction "5_9") (pintype "bidirectional"))
      (node (ref "R26") (pin "2") (pinfunction "2_2") (pintype "passive"))
      (node (ref "SW4") (pin "1") (pinfunction "1_1") (pintype "passive"))
      (node (ref "SW4") (pin "2") (pinfunction "2_2") (pintype "passive"))
      (node (ref "SW9") (pin "4") (pinfunction "4_4") (pintype "passive"))
      (node (ref "U4") (pin "7") (pinfunction "OUT_7") (pintype "output"))
    )
    (net (code "69") (name "OUT5") (class "Default")
      (node (ref "C13") (pin "1") (pinfunction "1_1") (pintype "passive"))
      (node (ref "OUTPUTS") (pin "7") (pinfunction "4_7") (pintype "bidirectional"))
      (node (ref "OUTPUTS") (pin "8") (pinfunction "4_8") (pintype "bidirectional"))
      (node (ref "R33") (pin "2") (pinfunction "2_2") (pintype "passive"))
      (node (ref "SW5") (pin "1") (pinfunction "1_1") (pintype "passive"))
      (node (ref "SW5") (pin "2") (pinfunction "2_2") (pintype "passive"))
      (node (ref "SW9") (pin "5") (pinfunction "5_5") (pintype "passive"))
      (node (ref "U5") (pin "7") (pinfunction "OUT_7") (pintype "output"))
    )
    (net (code "70") (name "OUT6") (class "Default")
      (node (ref "C15") (pin "1") (pinfunction "1_1") (pintype "passive"))
      (node (ref "OUTPUTS") (pin "5") (pinfunction "3_5") (pintype "bidirectional"))
      (node (ref "OUTPUTS") (pin "6") (pinfunction "3_6") (pintype "bidirectional"))
      (node (ref "R40") (pin "2") (pinfunction "2_2") (pintype "passive"))
      (node (ref "SW6") (pin "1") (pinfunction "1_1") (pintype "passive"))
      (node (ref "SW6") (pin "2") (pinfunction "2_2") (pintype "passive"))
      (node (ref "SW9") (pin "6") (pinfunction "6_6") (pintype "passive"))
      (node (ref "U6") (pin "7") (pinfunction "OUT_7") (pintype "output"))
    )
    (net (code "71") (name "OUT7") (class "Default")
      (node (ref "C17") (pin "1") (pinfunction "1_1") (pintype "passive"))
      (node (ref "OUTPUTS") (pin "3") (pinfunction "2_3") (pintype "bidirectional"))
      (node (ref "OUTPUTS") (pin "4") (pinfunction "2_4") (pintype "bidirectional"))
      (node (ref "R47") (pin "2") (pinfunction "2_2") (pintype "passive"))
      (node (ref "SW7") (pin "1") (pinfunction "1_1") (pintype "passive"))
      (node (ref "SW7") (pin "2") (pinfunction "2_2") (pintype "passive"))
      (node (ref "SW9") (pin "7") (pinfunction "7_7") (pintype "passive"))
      (node (ref "U7") (pin "7") (pinfunction "OUT_7") (pintype "output"))
    )
    (net (code "72") (name "OUT8") (class "Default")
      (node (ref "C19") (pin "1") (pinfunction "1_1") (pintype "passive"))
      (node (ref "OUTPUTS") (pin "1") (pinfunction "1_1") (pintype "bidirectional"))
      (node (ref "OUTPUTS") (pin "2") (pinfunction "1_2") (pintype "bidirectional"))
      (node (ref "R54") (pin "2") (pinfunction "2_2") (pintype "passive"))
      (node (ref "SW8") (pin "1") (pinfunction "1_1") (pintype "passive"))
      (node (ref "SW8") (pin "2") (pinfunction "2_2") (pintype "passive"))
      (node (ref "SW9") (pin "8") (pinfunction "8_8") (pintype "passive"))
      (node (ref "U8") (pin "7") (pinfunction "OUT_7") (pintype "output"))
    )
    (net (code "73") (name "SG_1") (class "Default")
      (node (ref "SG_CONN") (pin "1") (pinfunction "1_1") (pintype "bidirectional"))
      (node (ref "SG_CONN") (pin "2") (pinfunction "1_2") (pintype "bidirectional"))
      (node (ref "TRIM_1") (pin "2") (pinfunction "WIPER_2") (pintype "passive"))
      (node (ref "U1") (pin "2") (pinfunction "-IN_2") (pintype "input"))
    )
    (net (code "74") (name "SG_2") (class "Default")
      (node (ref "SG_CONN") (pin "5") (pinfunction "3_5") (pintype "bidirectional"))
      (node (ref "SG_CONN") (pin "6") (pinfunction "3_6") (pintype "bidirectional"))
      (node (ref "TRIM_2") (pin "2") (pinfunction "WIPER_2") (pintype "passive"))
      (node (ref "U2") (pin "2") (pinfunction "-IN_2") (pintype "input"))
    )
    (net (code "75") (name "SG_3") (class "Default")
      (node (ref "SG_CONN") (pin "10") (pinfunction "5_10") (pintype "bidirectional"))
      (node (ref "SG_CONN") (pin "9") (pinfunction "5_9") (pintype "bidirectional"))
      (node (ref "TRIM_3") (pin "2") (pinfunction "WIPER_2") (pintype "passive"))
      (node (ref "U3") (pin "2") (pinfunction "-IN_2") (pintype "input"))
    )
    (net (code "76") (name "SG_4") (class "Default")
      (node (ref "SG_CONN") (pin "13") (pinfunction "7_13") (pintype "bidirectional"))
      (node (ref "SG_CONN") (pin "14") (pinfunction "7_14") (pintype "bidirectional"))
      (node (ref "TRIM_4") (pin "2") (pinfunction "WIPER_2") (pintype "passive"))
      (node (ref "U4") (pin "2") (pinfunction "-IN_2") (pintype "input"))
    )
    (net (code "77") (name "SG_5") (class "Default")
      (node (ref "SG_CONN") (pin "17") (pinfunction "9_17") (pintype "bidirectional"))
      (node (ref "SG_CONN") (pin "18") (pinfunction "9_18") (pintype "bidirectional"))
      (node (ref "TRIM_5") (pin "2") (pinfunction "WIPER_2") (pintype "passive"))
      (node (ref "U5") (pin "2") (pinfunction "-IN_2") (pintype "input"))
    )
    (net (code "78") (name "SG_6") (class "Default")
      (node (ref "SG_CONN") (pin "21") (pinfunction "11_21") (pintype "bidirectional"))
      (node (ref "SG_CONN") (pin "22") (pinfunction "11_22") (pintype "bidirectional"))
      (node (ref "TRIM_6") (pin "2") (pinfunction "WIPER_2") (pintype "passive"))
      (node (ref "U6") (pin "2") (pinfunction "-IN_2") (pintype "input"))
    )
    (net (code "79") (name "SG_7") (class "Default")
      (node (ref "SG_CONN") (pin "25") (pinfunction "13_25") (pintype "bidirectional"))
      (node (ref "SG_CONN") (pin "26") (pinfunction "13_26") (pintype "bidirectional"))
      (node (ref "TRIM_7") (pin "2") (pinfunction "WIPER_2") (pintype "passive"))
      (node (ref "U7") (pin "2") (pinfunction "-IN_2") (pintype "input"))
    )
    (net (code "80") (name "SG_8") (class "Default")
      (node (ref "SG_CONN") (pin "29") (pinfunction "15_29") (pintype "bidirectional"))
      (node (ref "SG_CONN") (pin "30") (pinfunction "15_30") (pintype "bidirectional"))
      (node (ref "TRIM_8") (pin "2") (pinfunction "WIPER_2") (pintype "passive"))
      (node (ref "U8") (pin "2") (pinfunction "-IN_2") (pintype "input"))
    )
    (net (code "81") (name "UPP_V") (class "Default")
      (node (ref "IC1") (pin "5") (pinfunction "+IN_5") (pintype "input"))
      (node (ref "R59") (pin "1") (pinfunction "1_1") (pintype "passive"))
      (node (ref "R60") (pin "2") (pinfunction "2_2") (pintype "passive"))
    )
    (net (code "82") (name "unconnected-(TRIM_1-CCW-Pad1)") (class "Default")
      (node (ref "TRIM_1") (pin "1") (pinfunction "CCW_1") (pintype "passive"))
    )
    (net (code "83") (name "unconnected-(TRIM_2-CCW-Pad1)") (class "Default")
      (node (ref "TRIM_2") (pin "1") (pinfunction "CCW_1") (pintype "passive"))
    )
    (net (code "84") (name "unconnected-(TRIM_3-CCW-Pad1)") (class "Default")
      (node (ref "TRIM_3") (pin "1") (pinfunction "CCW_1") (pintype "passive"))
    )
    (net (code "85") (name "unconnected-(TRIM_4-CCW-Pad1)") (class "Default")
      (node (ref "TRIM_4") (pin "1") (pinfunction "CCW_1") (pintype "passive"))
    )
    (net (code "86") (name "unconnected-(TRIM_5-CCW-Pad1)") (class "Default")
      (node (ref "TRIM_5") (pin "1") (pinfunction "CCW_1") (pintype "passive"))
    )
    (net (code "87") (name "unconnected-(TRIM_6-CCW-Pad1)") (class "Default")
      (node (ref "TRIM_6") (pin "1") (pinfunction "CCW_1") (pintype "passive"))
    )
    (net (code "88") (name "unconnected-(TRIM_7-CCW-Pad1)") (class "Default")
      (node (ref "TRIM_7") (pin "1") (pinfunction "CCW_1") (pintype "passive"))
    )
    (net (code "89") (name "unconnected-(TRIM_8-CCW-Pad1)") (class "Default")
      (node (ref "TRIM_8") (pin "1") (pinfunction "CCW_1") (pintype "passive"))
    )
  )
)
